# supply.net
KiCad netlist of a schematic drawn in Altium Designer
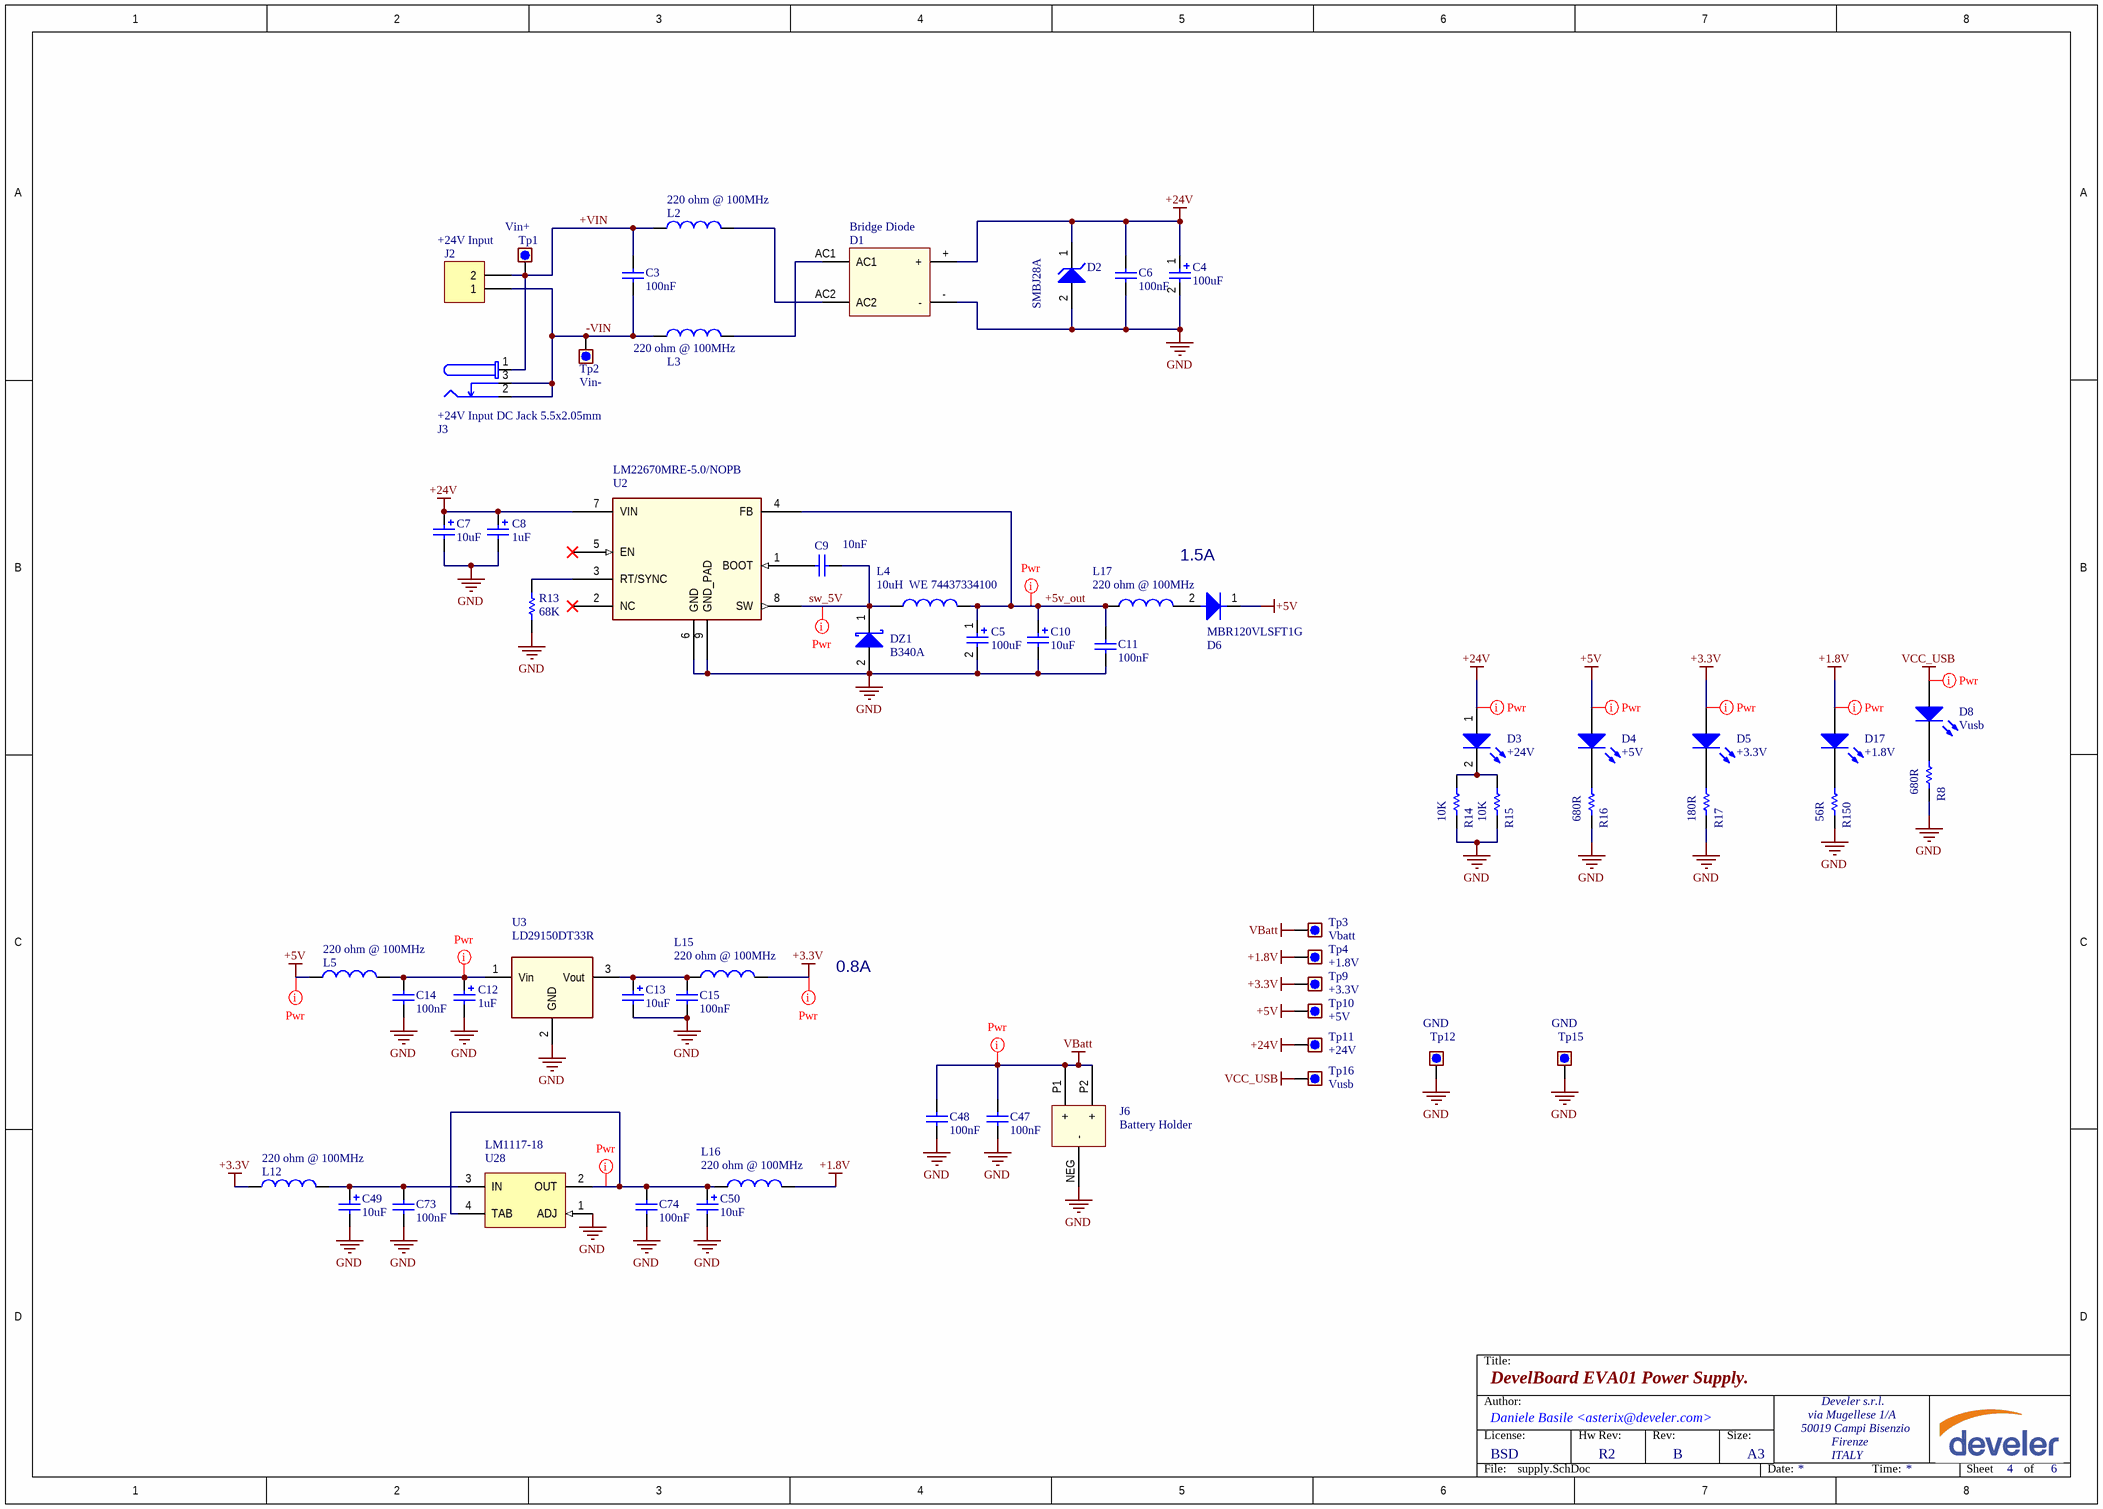
[diagram p0: supply.SchDoc]

(export (version "E")
  (design (tool "Eeschema 10.0.6"))
  (components
    (comp (ref "C3")
      (value "100nF")
      (footprint "0603_[1608]")
      (description "Ceramic X7R 50V")
      (fields (field (name "PUBLISHER") "Altium Limited"))
      (libsource (lib "DEVELER_Library") (part "Cap"))
    )
    (comp (ref "C4")
      (value "100uF")
      (footprint "CAP_6x6_D8_SMD")
      (description "EEEFK1H101P SMT 6x6 35V")
      (fields (field (name "PUBLISHER") "Altium Limited"))
      (libsource (lib "DEVELER_Library") (part "Cap Pol1"))
    )
    (comp (ref "C5")
      (value "100uF")
      (footprint "[7343]_CAP_TAN")
      (description "Tantalum 10V (T495D107K010ATE100)")
      (fields (field (name "PUBLISHER") "Altium Limited"))
      (libsource (lib "DEVELER_Library") (part "Cap Pol1"))
    )
    (comp (ref "C6")
      (value "100nF")
      (footprint "0603_[1608]")
      (description "Ceramic X7R 50V")
      (fields (field (name "PUBLISHER") "Altium Limited"))
      (libsource (lib "DEVELER_Library") (part "Cap"))
    )
    (comp (ref "C7")
      (value "10uF")
      (footprint "1206_[3216]")
      (description "Ceramic X5R 25V")
      (fields (field (name "PUBLISHER") "Altium Limited"))
      (libsource (lib "") (part "Cap Pol1_1"))
    )
    (comp (ref "C8")
      (value "1uF")
      (footprint "1206_[3216]")
      (description "Ceramic X7R 50V")
      (fields (field (name "PUBLISHER") "Altium Limited"))
      (libsource (lib "") (part "Cap Pol1_1"))
    )
    (comp (ref "C9")
      (value "10nF")
      (footprint "0603_[1608]")
      (description "Ceramic X7R 50V")
      (fields (field (name "PUBLISHER") "Altium Limited"))
      (libsource (lib "Miscellaneous Devices") (part "Cap"))
    )
    (comp (ref "C10")
      (value "10uF")
      (footprint "1206_[3216]")
      (description "Ceramic X5R 25V")
      (fields (field (name "PUBLISHER") "Altium Limited"))
      (libsource (lib "") (part "Cap Pol1_1"))
    )
    (comp (ref "C11")
      (value "100nF")
      (footprint "0603_[1608]")
      (description "Ceramic X7R 50V")
      (fields (field (name "PUBLISHER") "Altium Limited"))
      (libsource (lib "DEVELER_Library") (part "Cap"))
    )
    (comp (ref "C12")
      (value "1uF")
      (footprint "1206_[3216]")
      (description "Ceramic X7R 50V")
      (fields (field (name "PUBLISHER") "Altium Limited"))
      (libsource (lib "") (part "Cap Pol1_1"))
    )
    (comp (ref "C13")
      (value "10uF")
      (footprint "1206_[3216]")
      (description "Ceramic X5R 25V")
      (fields (field (name "PUBLISHER") "Altium Limited"))
      (libsource (lib "") (part "Cap Pol1_1"))
    )
    (comp (ref "C14")
      (value "100nF")
      (footprint "0603_[1608]")
      (description "Ceramic X7R 50V")
      (fields (field (name "PUBLISHER") "Altium Limited"))
      (libsource (lib "DEVELER_Library") (part "Cap"))
    )
    (comp (ref "C15")
      (value "100nF")
      (footprint "0603_[1608]")
      (description "Ceramic X7R 50V")
      (fields (field (name "PUBLISHER") "Altium Limited"))
      (libsource (lib "DEVELER_Library") (part "Cap"))
    )
    (comp (ref "C47")
      (value "100nF")
      (footprint "0603_[1608]")
      (description "Ceramic X7R 50V")
      (fields (field (name "PUBLISHER") "Altium Limited"))
      (libsource (lib "DEVELER_Library") (part "Cap"))
    )
    (comp (ref "C48")
      (value "100nF")
      (footprint "0603_[1608]")
      (description "Ceramic X7R 50V")
      (fields (field (name "PUBLISHER") "Altium Limited"))
      (libsource (lib "DEVELER_Library") (part "Cap"))
    )
    (comp (ref "C49")
      (value "10uF")
      (footprint "1206_[3216]")
      (description "Ceramic X5R 25V")
      (fields (field (name "PUBLISHER") "Altium Limited"))
      (libsource (lib "") (part "Cap Pol1_1"))
    )
    (comp (ref "C50")
      (value "10uF")
      (footprint "1206_[3216]")
      (description "Ceramic X5R 25V")
      (fields (field (name "PUBLISHER") "Altium Limited"))
      (libsource (lib "") (part "Cap Pol1_1"))
    )
    (comp (ref "C73")
      (value "100nF")
      (footprint "0603_[1608]")
      (description "Ceramic X7R 50V")
      (fields (field (name "PUBLISHER") "Altium Limited"))
      (libsource (lib "DEVELER_Library") (part "Cap"))
    )
    (comp (ref "C74")
      (value "100nF")
      (footprint "0603_[1608]")
      (description "Ceramic X7R 50V")
      (fields (field (name "PUBLISHER") "Altium Limited"))
      (libsource (lib "DEVELER_Library") (part "Cap"))
    )
    (comp (ref "D1")
      (value "Bridge Diode")
      (footprint "Diode_bridge_smd")
      (description "MBS4 (Farnell cod:4084985)")
      (libsource (lib "DEVELER_Library") (part "Diode_bridge2"))
    )
    (comp (ref "D2")
      (value "SMBJ28A")
      (footprint "DO214AA_12")
      (description "TRANSIL (SM6T12A)")
      (fields (field (name "PUBLISHER") "Altium Limited"))
      (libsource (lib "DEVELER_Library") (part "D Zener"))
    )
    (comp (ref "D3")
      (value "+24V")
      (footprint "0603_[1608]_LED")
      (description "LED Green")
      (fields (field (name "PUBLISHER") "Altium Limited"))
      (libsource (lib "") (part "LED0_1"))
    )
    (comp (ref "D4")
      (value "+5V")
      (footprint "0603_[1608]_LED")
      (description "LED Green")
      (fields (field (name "PUBLISHER") "Altium Limited"))
      (libsource (lib "DEVELER_Library") (part "LED0"))
    )
    (comp (ref "D5")
      (value "+3.3V")
      (footprint "0603_[1608]_LED")
      (description "LED Green")
      (fields (field (name "PUBLISHER") "Altium Limited"))
      (libsource (lib "DEVELER_Library") (part "LED0"))
    )
    (comp (ref "D6")
      (value "MBR120VLSFT1G")
      (footprint "SOD-123")
      (description "Diode Schottky  low Vf, If 1A (PMEG3010ER; MBRX120LF)")
      (libsource (lib "DEVELER_Library") (part "Diode"))
    )
    (comp (ref "D8")
      (value "Vusb")
      (footprint "0603_[1608]_LED")
      (description "LED Green")
      (fields (field (name "PUBLISHER") "Altium Limited"))
      (libsource (lib "DEVELER_Library") (part "LED0"))
    )
    (comp (ref "D17")
      (value "+1.8V")
      (footprint "0603_[1608]_LED")
      (description "LED Green")
      (fields (field (name "PUBLISHER") "Altium Limited"))
      (libsource (lib "DEVELER_Library") (part "LED0"))
    )
    (comp (ref "DZ1")
      (value "B340A")
      (footprint "DO214AA_12")
      (description "Diode Schottky (STPS2L40U)")
      (fields (field (name "PUBLISHER") "Altium Limited"))
      (libsource (lib "Miscellaneous Devices") (part "D Schottky"))
    )
    (comp (ref "J2")
      (value "+24V Input")
      (footprint "TBLOCK_1X2_3.5MM_HOR_THD")
      (description "Terminal block Header 3.5mm Horizontal (WE 691322110002)")
      (fields (field (name "PUBLISHER") "Altium Limited"))
      (libsource (lib "Miscellaneous Connectors") (part "Header 2"))
    )
    (comp (ref "J3")
      (value "+24V Input DC Jack 5.5x2.05mm")
      (footprint "DC_Jack_6.5x2.5mm_right_tht")
      (description "WR-DC_DC Power Jack_Right Angled_THT (WE  694106301002)")
      (fields
        (field (name "MANUFACTURER") "Würth Elektronik eiSos GmbH")
        (field (name "PARTNO") "694108301002")
        (field (name "CREATED BY") "Karrer Zheng")
      )
      (libsource (lib "DEVELER_Library") (part "WE-DC Power Jack 694108301002"))
    )
    (comp (ref "J6")
      (value "Battery Holder")
      (footprint "Battery_holder_16mm_thd")
      (description "CR1612/1616/1620/1632 (3013, Keystone)")
      (libsource (lib "DEVELER_Library") (part "Battery_holder_3002"))
    )
    (comp (ref "L2")
      (value "220 ohm @ 100MHz")
      (footprint "0805_[2012]")
      (description "Ferrite Beat (WE 742792022)")
      (fields (field (name "PUBLISHER") "Altium Limited"))
      (libsource (lib "DEVELER_Library") (part "Inductor"))
    )
    (comp (ref "L3")
      (value "220 ohm @ 100MHz")
      (footprint "0805_[2012]")
      (description "Ferrite Beat (WE 742792022)")
      (fields (field (name "PUBLISHER") "Altium Limited"))
      (libsource (lib "DEVELER_Library") (part "Inductor"))
    )
    (comp (ref "L4")
      (value "10uH  WE 74437334100")
      (footprint "WE-LHMI_5020")
      (description "SMD Shielded Tiny Power Inductor")
      (fields (field (name "PUBLISHER") "Altium Limited"))
      (libsource (lib "Miscellaneous Devices") (part "Inductor"))
    )
    (comp (ref "L5")
      (value "220 ohm @ 100MHz")
      (footprint "0805_[2012]")
      (description "Ferrite Beat (WE 742792022)")
      (fields (field (name "PUBLISHER") "Altium Limited"))
      (libsource (lib "DEVELER_Library") (part "Inductor"))
    )
    (comp (ref "L12")
      (value "220 ohm @ 100MHz")
      (footprint "0805_[2012]")
      (description "Ferrite Beat (WE 742792022)")
      (fields (field (name "PUBLISHER") "Altium Limited"))
      (libsource (lib "DEVELER_Library") (part "Inductor"))
    )
    (comp (ref "L15")
      (value "220 ohm @ 100MHz")
      (footprint "0805_[2012]")
      (description "Ferrite Beat (WE 742792022)")
      (libsource (lib "") (part "Inductor_1"))
    )
    (comp (ref "L16")
      (value "220 ohm @ 100MHz")
      (footprint "0805_[2012]")
      (description "Ferrite Beat (WE 742792022)")
      (libsource (lib "") (part "Inductor_1"))
    )
    (comp (ref "L17")
      (value "220 ohm @ 100MHz")
      (footprint "0805_[2012]")
      (description "Ferrite Beat (WE 742792022)")
      (libsource (lib "") (part "Inductor_1"))
    )
    (comp (ref "R8")
      (value "680R")
      (footprint "0603_[1608]")
      (description "Resistor")
      (libsource (lib "DEVELER_Library") (part "Res1"))
    )
    (comp (ref "R13")
      (value "68K")
      (footprint "0603_[1608]")
      (description "Resistor")
      (libsource (lib "DEVELER_Library") (part "Res1"))
    )
    (comp (ref "R14")
      (value "10K")
      (footprint "0603_[1608]")
      (description "Resistor")
      (libsource (lib "DEVELER_Library") (part "Res1"))
    )
    (comp (ref "R15")
      (value "10K")
      (footprint "0603_[1608]")
      (description "Resistor")
      (libsource (lib "DEVELER_Library") (part "Res1"))
    )
    (comp (ref "R16")
      (value "680R")
      (footprint "0603_[1608]")
      (description "Resistor")
      (libsource (lib "DEVELER_Library") (part "Res1"))
    )
    (comp (ref "R17")
      (value "180R")
      (footprint "0603_[1608]")
      (description "Resistor")
      (libsource (lib "DEVELER_Library") (part "Res1"))
    )
    (comp (ref "R150")
      (value "56R")
      (footprint "0603_[1608]")
      (description "Resistor")
      (libsource (lib "DEVELER_Library") (part "Res1"))
    )
    (comp (ref "Tp1")
      (value "Vin+")
      (footprint "TEST_POINT_THD_D1.6MM")
      (description "Test point")
      (libsource (lib "") (part "Test_point_1"))
    )
    (comp (ref "Tp2")
      (value "Vin-")
      (footprint "TEST_POINT_THD_D1.6MM")
      (description "Test point")
      (libsource (lib "") (part "Test_point_2"))
    )
    (comp (ref "Tp3")
      (value "Vbatt")
      (footprint "TEST_POINT_THD_D1.8MM")
      (description "Test point")
      (libsource (lib "DEVELER_Library") (part "Test_point"))
    )
    (comp (ref "Tp4")
      (value "+1.8V")
      (footprint "TEST_POINT_THD_D1.8MM")
      (description "Test point")
      (libsource (lib "DEVELER_Library") (part "Test_point"))
    )
    (comp (ref "Tp9")
      (value "+3.3V")
      (footprint "TEST_POINT_THD_D1.8MM")
      (description "Test point")
      (libsource (lib "DEVELER_Library") (part "Test_point"))
    )
    (comp (ref "Tp10")
      (value "+5V")
      (footprint "TEST_POINT_THD_D1.8MM")
      (description "Test point")
      (libsource (lib "DEVELER_Library") (part "Test_point"))
    )
    (comp (ref "Tp11")
      (value "+24V")
      (footprint "TEST_POINT_THD_D1.8MM")
      (description "Test point")
      (libsource (lib "DEVELER_Library") (part "Test_point"))
    )
    (comp (ref "Tp12")
      (value "GND")
      (footprint "TEST_POINT_THD_D1.8MM")
      (description "Test point")
      (libsource (lib "") (part "Test_point_1"))
    )
    (comp (ref "Tp15")
      (value "GND")
      (footprint "TEST_POINT_THD_D1.8MM")
      (description "Test point")
      (libsource (lib "") (part "Test_point_1"))
    )
    (comp (ref "Tp16")
      (value "Vusb")
      (footprint "TEST_POINT_THD_D1.8MM")
      (description "Test point")
      (libsource (lib "DEVELER_Library") (part "Test_point"))
    )
    (comp (ref "U2")
      (value "LM22670MRE-5.0/NOPB")
      (footprint "SOIC8_PAD")
      (description "Power switch")
      (libsource (lib "DEVELER_Library") (part "LM22670MR-ADJ"))
    )
    (comp (ref "U3")
      (value "LD29150DT33R")
      (footprint "TO-252_D2PAK_LARGEPAD")
      (description "Very Low Drop Linear regulator 3.3V (BA33BC0FP-E2; MIC2940A-3.3WU)")
      (libsource (lib "DEVELER_Library") (part "LD29150DT33R"))
    )
    (comp (ref "U28")
      (value "LM1117-18")
      (footprint "SOT-223")
      (description "LDO, Fixed Vout = 1.8V")
      (fields
        (field (name "PARTNUMBER") "LM317AEMP")
        (field (name "MANUFACTURER") "National Semiconductor")
        (field (name "PUBLISHER") "Altium Limited")
      )
      (libsource (lib "DEVELER_Library") (part "LM317AEMP"))
    )
  )
  (nets
    (net (code "1") (name "+1.8V") (class "Default")
      (node (ref "D17") (pin "1") (pinfunction "A_1") (pintype "passive"))
      (node (ref "L16") (pin "1") (pinfunction "1_1") (pintype "passive"))
      (node (ref "Tp4") (pin "1") (pinfunction "1_1") (pintype "passive"))
    )
    (net (code "2") (name "+3.3V") (class "Default")
      (node (ref "D5") (pin "1") (pinfunction "A_1") (pintype "passive"))
      (node (ref "L12") (pin "1") (pinfunction "1_1") (pintype "passive"))
      (node (ref "L15") (pin "1") (pinfunction "1_1") (pintype "passive"))
      (node (ref "Tp9") (pin "1") (pinfunction "1_1") (pintype "passive"))
    )
    (net (code "3") (name "+5V") (class "Default")
      (node (ref "D4") (pin "1") (pinfunction "A_1") (pintype "passive"))
      (node (ref "D6") (pin "1") (pinfunction "K_1") (pintype "passive"))
      (node (ref "L5") (pin "1") (pinfunction "1_1") (pintype "passive"))
      (node (ref "Tp10") (pin "1") (pinfunction "1_1") (pintype "passive"))
    )
    (net (code "4") (name "+24V") (class "Default")
      (node (ref "C4") (pin "1") (pinfunction "1_1") (pintype "passive"))
      (node (ref "C6") (pin "2") (pinfunction "2_2") (pintype "passive"))
      (node (ref "C7") (pin "1") (pinfunction "1_1") (pintype "passive"))
      (node (ref "C8") (pin "1") (pinfunction "1_1") (pintype "passive"))
      (node (ref "D1") (pin "+") (pinfunction "+_+") (pintype "passive"))
      (node (ref "D2") (pin "1") (pinfunction "K_1") (pintype "passive"))
      (node (ref "D3") (pin "1") (pinfunction "A_1") (pintype "passive"))
      (node (ref "Tp11") (pin "1") (pinfunction "1_1") (pintype "passive"))
      (node (ref "U2") (pin "7") (pinfunction "VIN_7") (pintype "power_in"))
    )
    (net (code "5") (name "/+5v_out") (class "Default")
      (node (ref "C10") (pin "1") (pinfunction "1_1") (pintype "passive"))
      (node (ref "C11") (pin "2") (pinfunction "2_2") (pintype "passive"))
      (node (ref "C5") (pin "1") (pinfunction "1_1") (pintype "passive"))
      (node (ref "L17") (pin "2") (pinfunction "2_2") (pintype "passive"))
      (node (ref "L4") (pin "2") (pinfunction "2_2") (pintype "passive"))
      (node (ref "U2") (pin "4") (pinfunction "FB_4") (pintype "passive"))
    )
    (net (code "6") (name "/+VIN") (class "Default")
      (node (ref "C3") (pin "2") (pinfunction "2_2") (pintype "passive"))
      (node (ref "J2") (pin "2") (pinfunction "2_2") (pintype "passive"))
      (node (ref "J3") (pin "1") (pinfunction "1_1") (pintype "power_in"))
      (node (ref "L2") (pin "1") (pinfunction "1_1") (pintype "passive"))
      (node (ref "Tp1") (pin "1") (pinfunction "1_1") (pintype "passive"))
    )
    (net (code "7") (name "/-VIN") (class "Default")
      (node (ref "C3") (pin "1") (pinfunction "1_1") (pintype "passive"))
      (node (ref "J2") (pin "1") (pinfunction "1_1") (pintype "passive"))
      (node (ref "J3") (pin "2") (pinfunction "2_2") (pintype "power_in"))
      (node (ref "J3") (pin "3") (pinfunction "3_3") (pintype "power_in"))
      (node (ref "L3") (pin "1") (pinfunction "1_1") (pintype "passive"))
      (node (ref "Tp2") (pin "1") (pinfunction "1_1") (pintype "passive"))
    )
    (net (code "8") (name "/sw_5V") (class "Default")
      (node (ref "C9") (pin "2") (pinfunction "2_2") (pintype "passive"))
      (node (ref "DZ1") (pin "1") (pinfunction "K_1") (pintype "passive"))
      (node (ref "L4") (pin "1") (pinfunction "1_1") (pintype "passive"))
      (node (ref "U2") (pin "8") (pinfunction "SW_8") (pintype "output"))
    )
    (net (code "9") (name "GND") (class "Default")
      (node (ref "C10") (pin "2") (pinfunction "2_2") (pintype "passive"))
      (node (ref "C11") (pin "1") (pinfunction "1_1") (pintype "passive"))
      (node (ref "C12") (pin "2") (pinfunction "2_2") (pintype "passive"))
      (node (ref "C13") (pin "2") (pinfunction "2_2") (pintype "passive"))
      (node (ref "C14") (pin "1") (pinfunction "1_1") (pintype "passive"))
      (node (ref "C15") (pin "1") (pinfunction "1_1") (pintype "passive"))
      (node (ref "C4") (pin "2") (pinfunction "2_2") (pintype "passive"))
      (node (ref "C47") (pin "1") (pinfunction "1_1") (pintype "passive"))
      (node (ref "C48") (pin "1") (pinfunction "1_1") (pintype "passive"))
      (node (ref "C49") (pin "2") (pinfunction "2_2") (pintype "passive"))
      (node (ref "C5") (pin "2") (pinfunction "2_2") (pintype "passive"))
      (node (ref "C50") (pin "2") (pinfunction "2_2") (pintype "passive"))
      (node (ref "C6") (pin "1") (pinfunction "1_1") (pintype "passive"))
      (node (ref "C7") (pin "2") (pinfunction "2_2") (pintype "passive"))
      (node (ref "C73") (pin "1") (pinfunction "1_1") (pintype "passive"))
      (node (ref "C74") (pin "1") (pinfunction "1_1") (pintype "passive"))
      (node (ref "C8") (pin "2") (pinfunction "2_2") (pintype "passive"))
      (node (ref "D1") (pin "-") (pinfunction "-_-") (pintype "passive"))
      (node (ref "D2") (pin "2") (pinfunction "A_2") (pintype "passive"))
      (node (ref "DZ1") (pin "2") (pinfunction "A_2") (pintype "passive"))
      (node (ref "J6") (pin "NEG") (pinfunction "-_NEG") (pintype "passive"))
      (node (ref "R13") (pin "1") (pinfunction "1_1") (pintype "passive"))
      (node (ref "R14") (pin "1") (pinfunction "1_1") (pintype "passive"))
      (node (ref "R15") (pin "1") (pinfunction "1_1") (pintype "passive"))
      (node (ref "R150") (pin "1") (pinfunction "1_1") (pintype "passive"))
      (node (ref "R16") (pin "1") (pinfunction "1_1") (pintype "passive"))
      (node (ref "R17") (pin "1") (pinfunction "1_1") (pintype "passive"))
      (node (ref "R8") (pin "1") (pinfunction "1_1") (pintype "passive"))
      (node (ref "Tp12") (pin "1") (pinfunction "1_1") (pintype "passive"))
      (node (ref "Tp15") (pin "1") (pinfunction "1_1") (pintype "passive"))
      (node (ref "U2") (pin "6") (pinfunction "GND_6") (pintype "power_in"))
      (node (ref "U2") (pin "9") (pinfunction "GND_PAD_9") (pintype "power_in"))
      (node (ref "U28") (pin "1") (pinfunction "ADJ_1") (pintype "input"))
      (node (ref "U3") (pin "2") (pinfunction "GND_2") (pintype "passive"))
    )
    (net (code "10") (name "Net-(D1-PadAC1)") (class "Default")
      (node (ref "D1") (pin "AC1") (pinfunction "AC1_AC1") (pintype "passive"))
      (node (ref "L3") (pin "2") (pinfunction "2_2") (pintype "passive"))
    )
    (net (code "11") (name "Net-(D1-PadAC2)") (class "Default")
      (node (ref "D1") (pin "AC2") (pinfunction "AC2_AC2") (pintype "passive"))
      (node (ref "L2") (pin "2") (pinfunction "2_2") (pintype "passive"))
    )
    (net (code "12") (name "Net-(D3-K)") (class "Default")
      (node (ref "D3") (pin "2") (pinfunction "K_2") (pintype "passive"))
      (node (ref "R14") (pin "2") (pinfunction "2_2") (pintype "passive"))
      (node (ref "R15") (pin "2") (pinfunction "2_2") (pintype "passive"))
    )
    (net (code "13") (name "Net-(D4-K)") (class "Default")
      (node (ref "D4") (pin "2") (pinfunction "K_2") (pintype "passive"))
      (node (ref "R16") (pin "2") (pinfunction "2_2") (pintype "passive"))
    )
    (net (code "14") (name "Net-(D5-K)") (class "Default")
      (node (ref "D5") (pin "2") (pinfunction "K_2") (pintype "passive"))
      (node (ref "R17") (pin "2") (pinfunction "2_2") (pintype "passive"))
    )
    (net (code "15") (name "Net-(D6-A)") (class "Default")
      (node (ref "D6") (pin "2") (pinfunction "A_2") (pintype "passive"))
      (node (ref "L17") (pin "1") (pinfunction "1_1") (pintype "passive"))
    )
    (net (code "16") (name "Net-(D8-K)") (class "Default")
      (node (ref "D8") (pin "2") (pinfunction "K_2") (pintype "passive"))
      (node (ref "R8") (pin "2") (pinfunction "2_2") (pintype "passive"))
    )
    (net (code "17") (name "Net-(D17-K)") (class "Default")
      (node (ref "D17") (pin "2") (pinfunction "K_2") (pintype "passive"))
      (node (ref "R150") (pin "2") (pinfunction "2_2") (pintype "passive"))
    )
    (net (code "18") (name "Net-(U2-BOOT)") (class "Default")
      (node (ref "C9") (pin "1") (pinfunction "1_1") (pintype "passive"))
      (node (ref "U2") (pin "1") (pinfunction "BOOT_1") (pintype "input"))
    )
    (net (code "19") (name "Net-(U2-RT{slash}SYNC)") (class "Default")
      (node (ref "R13") (pin "2") (pinfunction "2_2") (pintype "passive"))
      (node (ref "U2") (pin "3") (pinfunction "RT/SYNC_3") (pintype "passive"))
    )
    (net (code "20") (name "Net-(U3-Vin)") (class "Default")
      (node (ref "C12") (pin "1") (pinfunction "1_1") (pintype "passive"))
      (node (ref "C14") (pin "2") (pinfunction "2_2") (pintype "passive"))
      (node (ref "L5") (pin "2") (pinfunction "2_2") (pintype "passive"))
      (node (ref "U3") (pin "1") (pinfunction "Vin_1") (pintype "passive"))
    )
    (net (code "21") (name "Net-(U3-Vout)") (class "Default")
      (node (ref "C13") (pin "1") (pinfunction "1_1") (pintype "passive"))
      (node (ref "C15") (pin "2") (pinfunction "2_2") (pintype "passive"))
      (node (ref "L15") (pin "2") (pinfunction "2_2") (pintype "passive"))
      (node (ref "U3") (pin "3") (pinfunction "Vout_3") (pintype "passive"))
    )
    (net (code "22") (name "Net-(U28-IN)") (class "Default")
      (node (ref "C49") (pin "1") (pinfunction "1_1") (pintype "passive"))
      (node (ref "C73") (pin "2") (pinfunction "2_2") (pintype "passive"))
      (node (ref "L12") (pin "2") (pinfunction "2_2") (pintype "passive"))
      (node (ref "U28") (pin "3") (pinfunction "IN_3") (pintype "power_in"))
    )
    (net (code "23") (name "Net-(U28-OUT)") (class "Default")
      (node (ref "C50") (pin "1") (pinfunction "1_1") (pintype "passive"))
      (node (ref "C74") (pin "2") (pinfunction "2_2") (pintype "passive"))
      (node (ref "L16") (pin "2") (pinfunction "2_2") (pintype "passive"))
      (node (ref "U28") (pin "2") (pinfunction "OUT_2") (pintype "power_in"))
      (node (ref "U28") (pin "4") (pinfunction "TAB_4") (pintype "power_in"))
    )
    (net (code "24") (name "VBatt") (class "Default")
      (node (ref "C47") (pin "2") (pinfunction "2_2") (pintype "passive"))
      (node (ref "C48") (pin "2") (pinfunction "2_2") (pintype "passive"))
      (node (ref "J6") (pin "P1") (pinfunction "+_P1") (pintype "passive"))
      (node (ref "J6") (pin "P2") (pinfunction "+_P2") (pintype "passive"))
      (node (ref "Tp3") (pin "1") (pinfunction "1_1") (pintype "passive"))
    )
    (net (code "25") (name "VCC_USB") (class "Default")
      (node (ref "D8") (pin "1") (pinfunction "A_1") (pintype "passive"))
      (node (ref "Tp16") (pin "1") (pinfunction "1_1") (pintype "passive"))
    )
    (net (code "26") (name "unconnected-(U2-EN-Pad5)") (class "Default")
      (node (ref "U2") (pin "5") (pinfunction "EN_5") (pintype "input+no_connect"))
    )
    (net (code "27") (name "unconnected-(U2-NC-Pad2)") (class "Default")
      (node (ref "U2") (pin "2") (pinfunction "NC_2") (pintype "passive+no_connect"))
    )
  )
)
